# ADC.net
KiCad netlist of a schematic drawn in Altium Designer
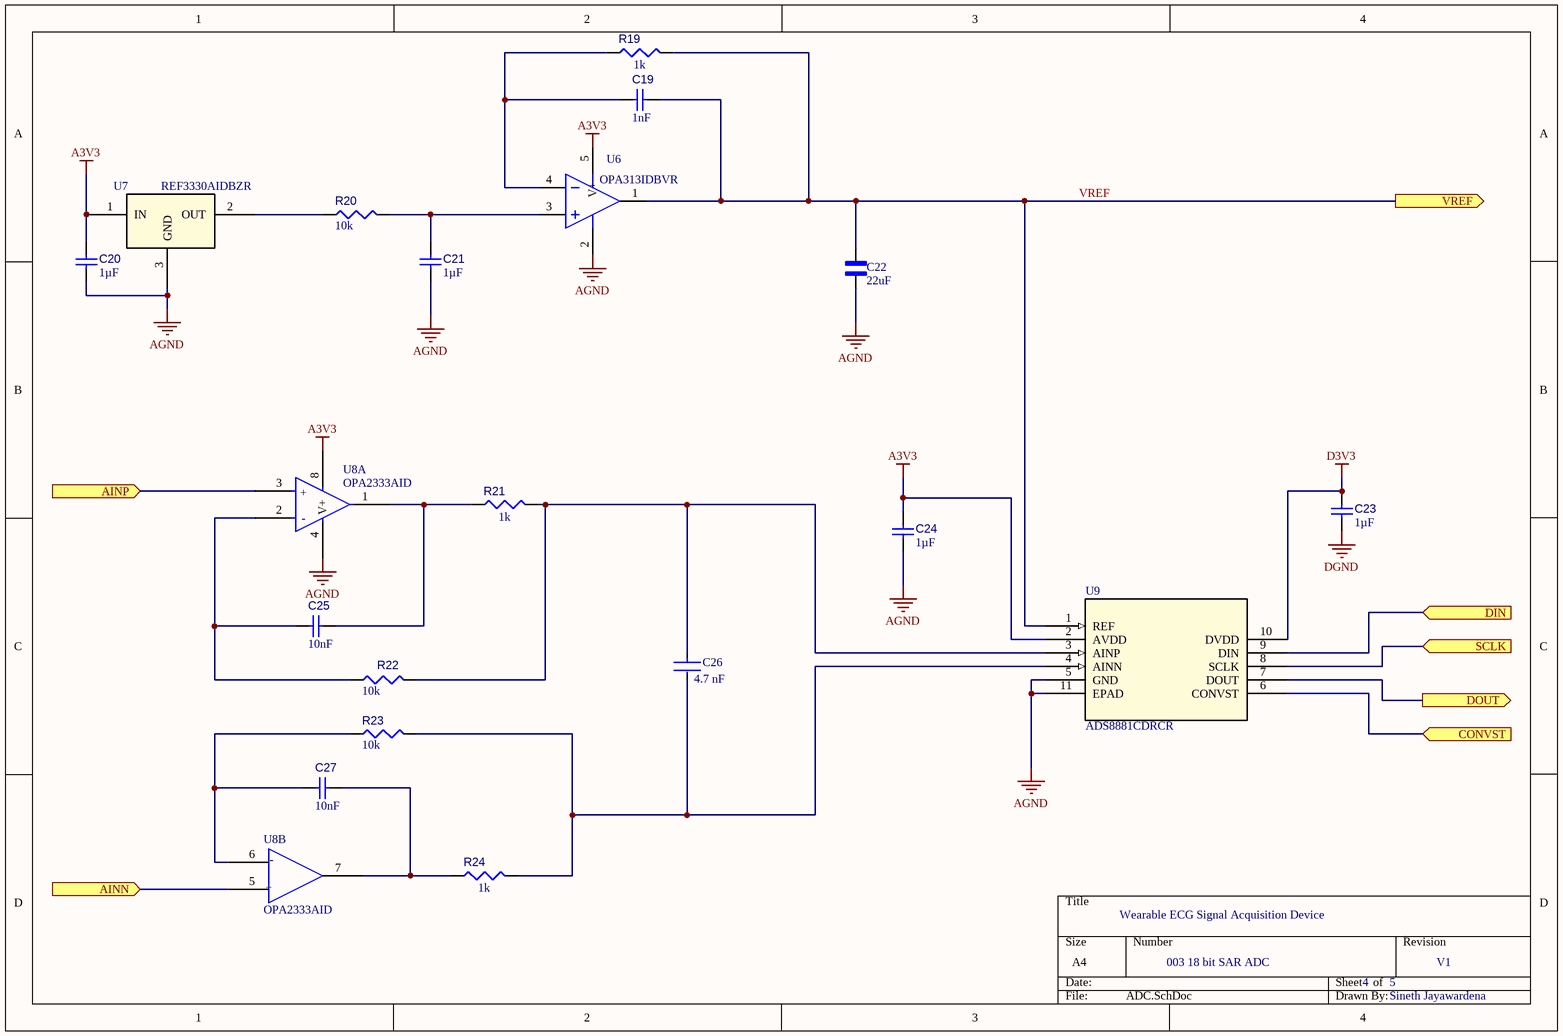
[diagram p0: ADC.SchDoc]

(export (version "E")
  (design (tool "Eeschema 10.0.6"))
  (components
    (comp (ref "C19")
      (value "1nF")
      (footprint "CAPC0402(1005)33_L")
      (description "Chip Capacitor, 1nF +/-20%, 50V, 0402, Thickness 0.33 mm")
      (fields (field (name "TOLERANCE") "10%") (field (name "Comment") "Capacitor 1nF +/-20% 50V 0402"))
      (libsource (lib "Sineth Jayawardena") (part "CAP-NP-2"))
    )
    (comp (ref "C20")
      (value "1µF")
      (footprint "CAPC2013X145X50ML20T25")
      (description "Chip Capacitor, 1 uF, +/-10%, 25 V, 0805 (2012 Metric)")
      (fields (field (name "TOLERANCE") "10%") (field (name "Comment") "Capacitor 1 uF +/- 10% 25 V 0805"))
      (libsource (lib "Sineth Jayawardena") (part "CAP-NP-2"))
    )
    (comp (ref "C21")
      (value "1µF")
      (footprint "CAPC2013X145X50ML20T25")
      (description "Chip Capacitor, 1 uF, +/-10%, 25 V, 0805 (2012 Metric)")
      (fields (field (name "TOLERANCE") "10%") (field (name "Comment") "Capacitor 1 uF +/- 10% 25 V 0805"))
      (libsource (lib "Sineth Jayawardena") (part "CAP-NP-2"))
    )
    (comp (ref "C22")
      (value "22uF")
      (footprint "22uF_CAPC1608X100N")
      (description "SMD capacitor X5R(EIA) with capacitance 22uF Tol.20%. Rated voltage 10Vdc 85C")
      (fields (field (name "MF") "Murata Electronics") (field (name "MP") "GRM188R61A226ME15D"))
      (libsource (lib "Schlib1") (part "22uF"))
    )
    (comp (ref "C23")
      (value "1µF")
      (footprint "CAPC2013X145X50ML20T25")
      (description "Chip Capacitor, 1 uF, +/-10%, 25 V, 0805 (2012 Metric)")
      (fields (field (name "TOLERANCE") "10%") (field (name "Comment") "Capacitor 1 uF +/- 10% 25 V 0805"))
      (libsource (lib "Sineth Jayawardena") (part "CAP-NP-2"))
    )
    (comp (ref "C24")
      (value "1µF")
      (footprint "CAPC2013X145X50ML20T25")
      (description "Chip Capacitor, 1 uF, +/-10%, 25 V, 0805 (2012 Metric)")
      (fields (field (name "TOLERANCE") "10%") (field (name "Comment") "Capacitor 1 uF +/- 10% 25 V 0805"))
      (libsource (lib "Sineth Jayawardena") (part "CAP-NP-2"))
    )
    (comp (ref "C25")
      (value "10nF")
      (footprint "CAPC0402(1005)60_L")
      (description "Chip Capacitor, 10nF +/-20%, 50V, 0402, Thickness 0.6 mm")
      (fields (field (name "TOLERANCE") "5%") (field (name "Comment") "Capacitor 10nF +/-20% 50V 0402"))
      (libsource (lib "Sineth Jayawardena") (part "CAP-NP-2"))
    )
    (comp (ref "C26")
      (value "4.7 nF")
      (footprint "FP-AC0805-0_85-MFG")
      (description "CAP CER 4700PF 100V X7R 0805")
      (fields (field (name "TOLERANCE") "0.1") (field (name "MANUFACTURER") "Yageo"))
      (libsource (lib "Altium Content Vault") (part "11868f565c42a9108669ba33697ecf6"))
    )
    (comp (ref "C27")
      (value "10nF")
      (footprint "CAPC0402(1005)60_L")
      (description "Chip Capacitor, 10nF +/-20%, 50V, 0402, Thickness 0.6 mm")
      (fields (field (name "TOLERANCE") "5%") (field (name "Comment") "Capacitor 10nF +/-20% 50V 0402"))
      (libsource (lib "Sineth Jayawardena") (part "CAP-NP-2"))
    )
    (comp (ref "R19")
      (value "1k")
      (footprint "RESC0805(2012)_L")
      (description "Chip Resistor, 1 kOhms, +/-5%, 125 mW, -55 to 155 degC, 0805")
      (fields (field (name "TOLERANCE") "5%") (field (name "POWER") "125mW"))
      (libsource (lib "Sineth Jayawardena") (part "RES-2"))
    )
    (comp (ref "R20")
      (value "10k")
      (footprint "RESC2013X50X35NL15T15")
      (description "Chip Resistor, 10 KOhm, +/- 1%, 125 mW, -55 to 155 degC, 0805 (2012 Metric)")
      (fields (field (name "TOLERANCE") "1%") (field (name "POWER") "125mW"))
      (libsource (lib "Sineth Jayawardena") (part "RES-2"))
    )
    (comp (ref "R21")
      (value "1k")
      (footprint "RESC0805(2012)_L")
      (description "Chip Resistor, 1 kOhms, +/-5%, 125 mW, -55 to 155 degC, 0805")
      (fields (field (name "TOLERANCE") "5%") (field (name "POWER") "125mW"))
      (libsource (lib "Sineth Jayawardena") (part "RES-2"))
    )
    (comp (ref "R22")
      (value "10k")
      (footprint "RESC2013X50X35NL15T15")
      (description "Chip Resistor, 10 KOhm, +/- 1%, 125 mW, -55 to 155 degC, 0805 (2012 Metric)")
      (fields (field (name "TOLERANCE") "1%") (field (name "POWER") "125mW"))
      (libsource (lib "Sineth Jayawardena") (part "RES-2"))
    )
    (comp (ref "R23")
      (value "10k")
      (footprint "RESC2013X50X35NL15T15")
      (description "Chip Resistor, 10 KOhm, +/- 1%, 125 mW, -55 to 155 degC, 0805 (2012 Metric)")
      (fields (field (name "TOLERANCE") "1%") (field (name "POWER") "125mW"))
      (libsource (lib "Sineth Jayawardena") (part "RES-2"))
    )
    (comp (ref "R24")
      (value "1k")
      (footprint "RESC0805(2012)_L")
      (description "Chip Resistor, 1 kOhms, +/-5%, 125 mW, -55 to 155 degC, 0805")
      (fields (field (name "TOLERANCE") "5%") (field (name "POWER") "125mW"))
      (libsource (lib "Sineth Jayawardena") (part "RES-2"))
    )
    (comp (ref "U6")
      (value "OPA313IDBVR")
      (footprint "DBV0005A_L")
      (fields (field (name "MANUFACTURER") "Texas Instruments"))
      (libsource (lib "Altium Content Vault") (part "TI-OPA313-DBV5"))
    )
    (comp (ref "U7")
      (value "REF3330AIDBZR")
      (footprint "DBZ3-M")
      (fields (field (name "COPYRIGHT") "Copyright (C) 2025 Ultra Librarian. All rights reserved."))
      (libsource (lib "Schlib1") (part "REF3330AIDBZR"))
    )
    (comp (ref "U8")
      (value "OPA2333AID")
      (footprint "OPA2333_D8-M")
      (description "1.8-V, 17-ÂµA, two-channel, micropower zero-drift CMOS operational amplifier 8-SOIC -40 to 125")
      (fields (field (name "COPYRIGHT") "Copyright (C) 2025 Ultra Librarian. All rights reserved."))
      (libsource (lib "Schlib1") (part "OPA2333AID"))
    )
    (comp (ref "U9")
      (value "ADS8881CDRCR")
      (footprint "ADC_DRC10_TEX-L")
      (fields (field (name "COPYRIGHT") "Copyright (C) 2025 Ultra Librarian. All rights reserved."))
      (libsource (lib "Schlib1") (part "ADS8881CDRCR"))
    )
  )
  (nets
    (net (code "1") (name "/AINN") (class "Default")
      (node (ref "U8") (pin "5") (pinfunction "INB+_5") (pintype "passive"))
    )
    (net (code "2") (name "/AINP") (class "Default")
      (node (ref "U8") (pin "3") (pinfunction "INA+_3") (pintype "passive"))
    )
    (net (code "3") (name "/CONVST") (class "Default")
      (node (ref "U9") (pin "6") (pinfunction "CONVST_6") (pintype "passive"))
    )
    (net (code "4") (name "/DIN") (class "Default")
      (node (ref "U9") (pin "9") (pinfunction "DIN_9") (pintype "passive"))
    )
    (net (code "5") (name "/DOUT") (class "Default")
      (node (ref "U9") (pin "7") (pinfunction "DOUT_7") (pintype "passive"))
    )
    (net (code "6") (name "/SCLK") (class "Default")
      (node (ref "U9") (pin "8") (pinfunction "SCLK_8") (pintype "passive"))
    )
    (net (code "7") (name "/VREF") (class "Default")
      (node (ref "C19") (pin "2") (pinfunction "2_2") (pintype "passive"))
      (node (ref "C22") (pin "2") (pinfunction "2_2") (pintype "passive"))
      (node (ref "R19") (pin "2") (pinfunction "2_2") (pintype "passive"))
      (node (ref "U6") (pin "1") (pinfunction "OUT_1") (pintype "passive"))
      (node (ref "U9") (pin "1") (pinfunction "REF_1") (pintype "input"))
    )
    (net (code "8") (name "A3V3") (class "Default")
      (node (ref "C20") (pin "2") (pinfunction "2_2") (pintype "passive"))
      (node (ref "C24") (pin "2") (pinfunction "2_2") (pintype "passive"))
      (node (ref "U6") (pin "5") (pinfunction "V+_5") (pintype "power_in"))
      (node (ref "U7") (pin "1") (pinfunction "IN_1") (pintype "passive"))
      (node (ref "U8") (pin "8") (pinfunction "V+_8") (pintype "power_in"))
      (node (ref "U9") (pin "2") (pinfunction "AVDD_2") (pintype "power_in"))
    )
    (net (code "9") (name "AGND") (class "Default")
      (node (ref "C20") (pin "1") (pinfunction "1_1") (pintype "passive"))
      (node (ref "C21") (pin "1") (pinfunction "1_1") (pintype "passive"))
      (node (ref "C22") (pin "1") (pinfunction "1_1") (pintype "passive"))
      (node (ref "C24") (pin "1") (pinfunction "1_1") (pintype "passive"))
      (node (ref "U6") (pin "2") (pinfunction "V-_2") (pintype "power_in"))
      (node (ref "U7") (pin "3") (pinfunction "GND_3") (pintype "power_in"))
      (node (ref "U8") (pin "4") (pinfunction "V-_4") (pintype "power_in"))
      (node (ref "U9") (pin "11") (pinfunction "EPAD_11") (pintype "passive"))
      (node (ref "U9") (pin "5") (pinfunction "GND_5") (pintype "power_in"))
    )
    (net (code "10") (name "D3V3") (class "Default")
      (node (ref "C23") (pin "2") (pinfunction "2_2") (pintype "passive"))
      (node (ref "U9") (pin "10") (pinfunction "DVDD_10") (pintype "passive"))
    )
    (net (code "11") (name "DGND") (class "Default")
      (node (ref "C23") (pin "1") (pinfunction "1_1") (pintype "passive"))
    )
    (net (code "12") (name "Net-(U6-IN+)") (class "Default")
      (node (ref "C21") (pin "2") (pinfunction "2_2") (pintype "passive"))
      (node (ref "R20") (pin "2") (pinfunction "2_2") (pintype "passive"))
      (node (ref "U6") (pin "3") (pinfunction "IN+_3") (pintype "passive"))
    )
    (net (code "13") (name "Net-(U6-IN-)") (class "Default")
      (node (ref "C19") (pin "1") (pinfunction "1_1") (pintype "passive"))
      (node (ref "R19") (pin "1") (pinfunction "1_1") (pintype "passive"))
      (node (ref "U6") (pin "4") (pinfunction "IN-_4") (pintype "passive"))
    )
    (net (code "14") (name "Net-(U7-OUT)") (class "Default")
      (node (ref "R20") (pin "1") (pinfunction "1_1") (pintype "passive"))
      (node (ref "U7") (pin "2") (pinfunction "OUT_2") (pintype "passive"))
    )
    (net (code "15") (name "Net-(U8A-INA-)") (class "Default")
      (node (ref "C25") (pin "1") (pinfunction "1_1") (pintype "passive"))
      (node (ref "R22") (pin "1") (pinfunction "1_1") (pintype "passive"))
      (node (ref "U8") (pin "2") (pinfunction "INA-_2") (pintype "passive"))
    )
    (net (code "16") (name "Net-(U8A-OUTA)") (class "Default")
      (node (ref "C25") (pin "2") (pinfunction "2_2") (pintype "passive"))
      (node (ref "R21") (pin "1") (pinfunction "1_1") (pintype "passive"))
      (node (ref "U8") (pin "1") (pinfunction "OUTA_1") (pintype "passive"))
    )
    (net (code "17") (name "Net-(U8B-INB-)") (class "Default")
      (node (ref "C27") (pin "1") (pinfunction "1_1") (pintype "passive"))
      (node (ref "R23") (pin "1") (pinfunction "1_1") (pintype "passive"))
      (node (ref "U8") (pin "6") (pinfunction "INB-_6") (pintype "passive"))
    )
    (net (code "18") (name "Net-(U8B-OUTB)") (class "Default")
      (node (ref "C27") (pin "2") (pinfunction "2_2") (pintype "passive"))
      (node (ref "R24") (pin "1") (pinfunction "1_1") (pintype "passive"))
      (node (ref "U8") (pin "7") (pinfunction "OUTB_7") (pintype "passive"))
    )
    (net (code "19") (name "Net-(U9-AINN)") (class "Default")
      (node (ref "C26") (pin "2") (pinfunction "2_2") (pintype "passive"))
      (node (ref "R23") (pin "2") (pinfunction "2_2") (pintype "passive"))
      (node (ref "R24") (pin "2") (pinfunction "2_2") (pintype "passive"))
      (node (ref "U9") (pin "4") (pinfunction "AINN_4") (pintype "input"))
    )
    (net (code "20") (name "Net-(U9-AINP)") (class "Default")
      (node (ref "C26") (pin "1") (pinfunction "1_1") (pintype "passive"))
      (node (ref "R21") (pin "2") (pinfunction "2_2") (pintype "passive"))
      (node (ref "R22") (pin "2") (pinfunction "2_2") (pintype "passive"))
      (node (ref "U9") (pin "3") (pinfunction "AINP_3") (pintype "input"))
    )
  )
)
